# LM2596.net
KiCad netlist of a schematic drawn in Altium Designer
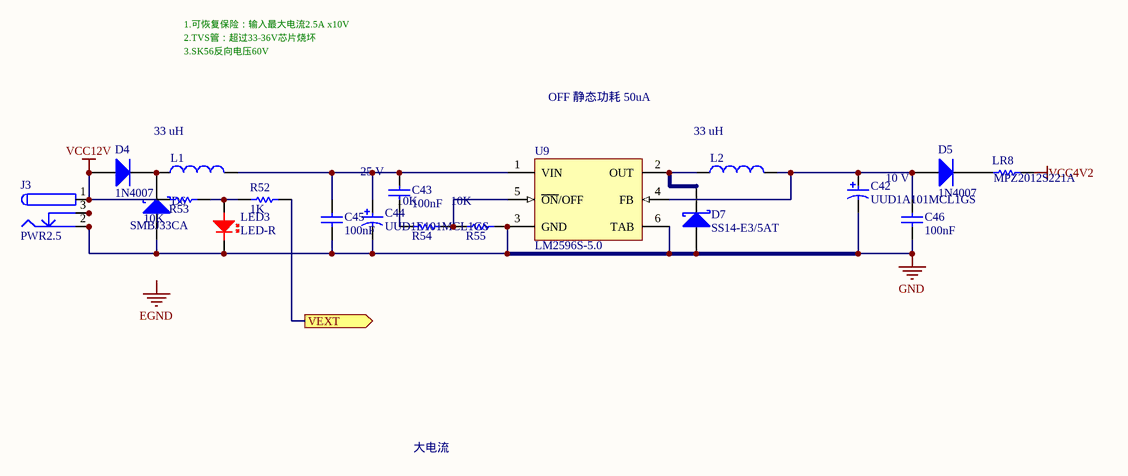
[diagram p0: LM2596.SchDoc]

(export (version "E")
  (design (tool "Eeschema 10.0.6"))
  (components
    (comp (ref "C42")
      (value "UUD1A101MCL1GS")
      (footprint "NIC-CAPA2-6.3X5.8_V")
      (fields (field (name "RATED VOLTAGE") "10 V") (field (name "MANUFACTURER") "Nichicon"))
      (libsource (lib "Altium Content Vault") (part "CMP-0687-00054-1"))
    )
    (comp (ref "C43")
      (value "100nF")
      (footprint "2012[0805]06CD")
      (description "CAP 100nF 50V ±5% 0805 (2012 Metric) Thickness 1mm SMD")
      (fields (field (name "TOLERANCE") "±5%") (field (name "Comment") "CAP 100nF 50V 0805(2012)"))
      (libsource (lib "Altium Content Vault") (part "CMP-1036-04418-1"))
    )
    (comp (ref "C44")
      (value "UUD1E101MCL1GS")
      (footprint "NIC-CAPA2-6.3X7.7_V")
      (fields (field (name "RATED VOLTAGE") "25 V") (field (name "MANUFACTURER") "Nichicon"))
      (libsource (lib "Altium Content Vault") (part "CMP-0687-00063-1"))
    )
    (comp (ref "C45")
      (value "100nF")
      (footprint "2012[0805]06CD")
      (description "CAP 100nF 50V ±5% 0805 (2012 Metric) Thickness 1mm SMD")
      (fields (field (name "TOLERANCE") "±5%") (field (name "Comment") "CAP 100nF 50V 0805(2012)"))
      (libsource (lib "Altium Content Vault") (part "CMP-1036-04418-1"))
    )
    (comp (ref "C46")
      (value "100nF")
      (footprint "2012[0805]06CD")
      (description "CAP 100nF 50V ±5% 0805 (2012 Metric) Thickness 1mm SMD")
      (fields (field (name "TOLERANCE") "±5%") (field (name "Comment") "CAP 100nF 50V 0805(2012)"))
      (libsource (lib "Altium Content Vault") (part "CMP-1036-04418-1"))
    )
    (comp (ref "D4")
      (value "1N4007")
      (footprint "DO-214AC/SMA")
      (description "1.0 Ampere General Purpose Rectifier")
      (fields (field (name "PUBLISHER") "Altium Limited"))
      (libsource (lib "FSC Discrete Rectifier") (part "1N4007"))
    )
    (comp (ref "D5")
      (value "1N4007")
      (footprint "DO-214AC/SMA")
      (description "1.0 Ampere General Purpose Rectifier")
      (fields (field (name "PUBLISHER") "Altium Limited"))
      (libsource (lib "FSC Discrete Rectifier") (part "1N4007"))
    )
    (comp (ref "D6")
      (value "SMBJ33CA")
      (footprint "DO-214AA/SMB")
      (description "TVS")
      (fields (field (name "MANUFACTURER") "Fairchild Semiconductor"))
      (libsource (lib "IR Rectifier - Schottky") (part "30BQ040"))
    )
    (comp (ref "D7")
      (value "SS14-E3/5AT")
      (footprint "VISH-DO-214AC-2_V")
      (fields (field (name "MANUFACTURER") "Vishay Semiconductor"))
      (libsource (lib "Altium Content Vault") (part "VISH-DSKY_A1K2-2"))
    )
    (comp (ref "J3")
      (value "PWR2.5")
      (footprint "KLD-0202")
      (description "Low Voltage Power Supply Connector")
      (fields (field (name "PUBLISHER") "Altium Limited"))
      (libsource (lib "Miscellaneous Connectors") (part "PWR2.5"))
    )
    (comp (ref "L1")
      (value "SLF7045T-330M1R1-H")
      (footprint "INDP5050X28N")
      (description "固定电感器 SMD Power Inductor")
      (fields
        (field (name "MANUFACTURER") "TDK")
        (field (name "INDUCTANCE") "33 uH")
        (field (name "TOLERANCE") "20 %")
      )
      (libsource (lib "Miscellaneous Devices") (part "Inductor"))
    )
    (comp (ref "L2")
      (value "SLF7045T-330M1R1-H")
      (footprint "INDP5050X28N")
      (description "固定电感器 SMD Power Inductor")
      (fields
        (field (name "MANUFACTURER") "TDK")
        (field (name "INDUCTANCE") "33 uH")
        (field (name "TOLERANCE") "20 %")
      )
      (libsource (lib "Miscellaneous Devices") (part "Inductor"))
    )
    (comp (ref "LED3")
      (value "LED-R")
      (footprint "0805LED")
      (description "红色LED")
      (libsource (lib "mylib") (part "LED-RED"))
    )
    (comp (ref "LR8")
      (value "MPZ2012S221A")
      (footprint "2012[0805]RL")
      (description "电磁干扰滤波珠子、扼流圈和阵列 Ferrite Chip Beads")
      (fields (field (name "MANUFACTURER") "TDK"))
      (libsource (lib "Miscellaneous Devices") (part "Res Semi"))
    )
    (comp (ref "R52")
      (value "1K")
      (footprint "2012[0805]R")
      (description "1K 0.125W 1% 0805 (2012 Metric)  SMD")
      (fields (field (name "TOLERANCE") "1 %") (field (name "POWER") "0.125 W"))
      (libsource (lib "Altium Content Vault") (part "CMP-1013-00510-1"))
    )
    (comp (ref "R53")
      (value "10K")
      (footprint "2012[0805]R")
      (description "10K 0.125W 1% 0805 (2012 Metric)  SMD")
      (fields (field (name "TOLERANCE") "1 %") (field (name "POWER") "0.125 W"))
      (libsource (lib "Altium Content Vault") (part "CMP-1013-00623-1"))
    )
    (comp (ref "R54")
      (value "10K")
      (footprint "2012[0805]R")
      (description "10K 0.125W 1% 0805 (2012 Metric)  SMD")
      (fields (field (name "TOLERANCE") "1 %") (field (name "POWER") "0.125 W"))
      (libsource (lib "Altium Content Vault") (part "CMP-1013-00623-1"))
    )
    (comp (ref "R55")
      (value "10K")
      (footprint "2012[0805]R")
      (description "10K 0.125W 1% 0805 (2012 Metric)  SMD")
      (fields (field (name "TOLERANCE") "1 %") (field (name "POWER") "0.125 W"))
      (libsource (lib "Altium Content Vault") (part "CMP-1013-00623-1"))
    )
    (comp (ref "U9")
      (value "LM2596S-5.0")
      (footprint "TS5B_N")
      (description "SIMPLE SWITCHER?Power Converter 150 KHz 3A Step-Down Voltage Regulator, 5-pin TO-263")
      (fields (field (name "MANUFACTURER") "National Semiconductor"))
      (libsource (lib "National Semiconductor Switcher") (part "LM2596S-5.0"))
    )
  )
  (nets
    (net (code "1") (name "/VEXT") (class "Default")
      (node (ref "R52") (pin "1") (pinfunction "1_1") (pintype "passive"))
    )
    (net (code "3") (name "GND") (class "Default")
      (node (ref "C42") (pin "2") (pinfunction "2_2") (pintype "passive"))
      (node (ref "C44") (pin "2") (pinfunction "2_2") (pintype "passive"))
      (node (ref "C45") (pin "2") (pinfunction "2_2") (pintype "passive"))
      (node (ref "C46") (pin "2") (pinfunction "2_2") (pintype "passive"))
      (node (ref "D6") (pin "1") (pinfunction "A_1") (pintype "passive"))
      (node (ref "D7") (pin "1") (pinfunction "A_1") (pintype "passive"))
      (node (ref "J3") (pin "2") (pinfunction "2_2") (pintype "power_in"))
      (node (ref "J3") (pin "2A") (pinfunction "2A_2A") (pintype "power_in"))
      (node (ref "J3") (pin "2B") (pinfunction "2B_2B") (pintype "power_in"))
      (node (ref "LED3") (pin "2") (pintype "passive"))
      (node (ref "R55") (pin "2") (pinfunction "2_2") (pintype "passive"))
      (node (ref "U9") (pin "3") (pinfunction "GND_3") (pintype "power_in"))
      (node (ref "U9") (pin "6") (pinfunction "TAB_6") (pintype "power_in"))
    )
    (net (code "4") (name "Net-(C43-Pad2)") (class "Default")
      (node (ref "C43") (pin "2") (pinfunction "2_2") (pintype "passive"))
      (node (ref "R54") (pin "1") (pinfunction "1_1") (pintype "passive"))
    )
    (net (code "5") (name "Net-(D4-K)") (class "Default")
      (node (ref "D4") (pin "2") (pinfunction "K_2") (pintype "passive"))
      (node (ref "D6") (pin "2") (pinfunction "K_2") (pintype "passive"))
      (node (ref "L1") (pin "1") (pinfunction "1_1") (pintype "passive"))
    )
    (net (code "6") (name "Net-(D5-A)") (class "Default")
      (node (ref "C42") (pin "1") (pinfunction "1_1") (pintype "passive"))
      (node (ref "C46") (pin "1") (pinfunction "1_1") (pintype "passive"))
      (node (ref "D5") (pin "1") (pinfunction "A_1") (pintype "passive"))
      (node (ref "L2") (pin "2") (pinfunction "2_2") (pintype "passive"))
      (node (ref "U9") (pin "4") (pinfunction "FB_4") (pintype "input"))
    )
    (net (code "7") (name "Net-(D5-K)") (class "Default")
      (node (ref "D5") (pin "2") (pinfunction "K_2") (pintype "passive"))
      (node (ref "LR8") (pin "1") (pinfunction "1_1") (pintype "passive"))
    )
    (net (code "8") (name "Net-(D7-K)") (class "Default")
      (node (ref "D7") (pin "2") (pinfunction "K_2") (pintype "passive"))
      (node (ref "L2") (pin "1") (pinfunction "1_1") (pintype "passive"))
      (node (ref "U9") (pin "2") (pinfunction "OUT_2") (pintype "power_in"))
    )
    (net (code "9") (name "Net-(J3-Pad3)") (class "Default")
      (node (ref "J3") (pin "3") (pinfunction "3_3") (pintype "power_in"))
      (node (ref "J3") (pin "3A") (pinfunction "3A_3A") (pintype "power_in"))
      (node (ref "J3") (pin "3B") (pinfunction "3B_3B") (pintype "power_in"))
    )
    (net (code "10") (name "Net-(LED3-Pad1)") (class "Default")
      (node (ref "LED3") (pin "1") (pintype "passive"))
      (node (ref "R52") (pin "2") (pinfunction "2_2") (pintype "passive"))
      (node (ref "R53") (pin "2") (pinfunction "2_2") (pintype "passive"))
    )
    (net (code "11") (name "Net-(U9-VIN)") (class "Default")
      (node (ref "C43") (pin "1") (pinfunction "1_1") (pintype "passive"))
      (node (ref "C44") (pin "1") (pinfunction "1_1") (pintype "passive"))
      (node (ref "C45") (pin "1") (pinfunction "1_1") (pintype "passive"))
      (node (ref "L1") (pin "2") (pinfunction "2_2") (pintype "passive"))
      (node (ref "U9") (pin "1") (pinfunction "VIN_1") (pintype "power_in"))
    )
    (net (code "12") (name "Net-(U9-~{ON}{slash}OFF)") (class "Default")
      (node (ref "R54") (pin "2") (pinfunction "2_2") (pintype "passive"))
      (node (ref "R55") (pin "1") (pinfunction "1_1") (pintype "passive"))
      (node (ref "U9") (pin "5") (pinfunction "~{ON}/OFF_5") (pintype "input"))
    )
    (net (code "13") (name "VCC4V2") (class "Default")
      (node (ref "LR8") (pin "2") (pinfunction "2_2") (pintype "passive"))
    )
    (net (code "14") (name "VCC12V") (class "Default")
      (node (ref "D4") (pin "1") (pinfunction "A_1") (pintype "passive"))
      (node (ref "J3") (pin "1") (pinfunction "1_1") (pintype "power_in"))
      (node (ref "J3") (pin "1A") (pinfunction "1A_1A") (pintype "power_in"))
      (node (ref "J3") (pin "1B") (pinfunction "1B_1B") (pintype "power_in"))
      (node (ref "R53") (pin "1") (pinfunction "1_1") (pintype "passive"))
    )
  )
)
